# RVP_OVP_LC.net
KiCad netlist of a schematic drawn in Altium Designer
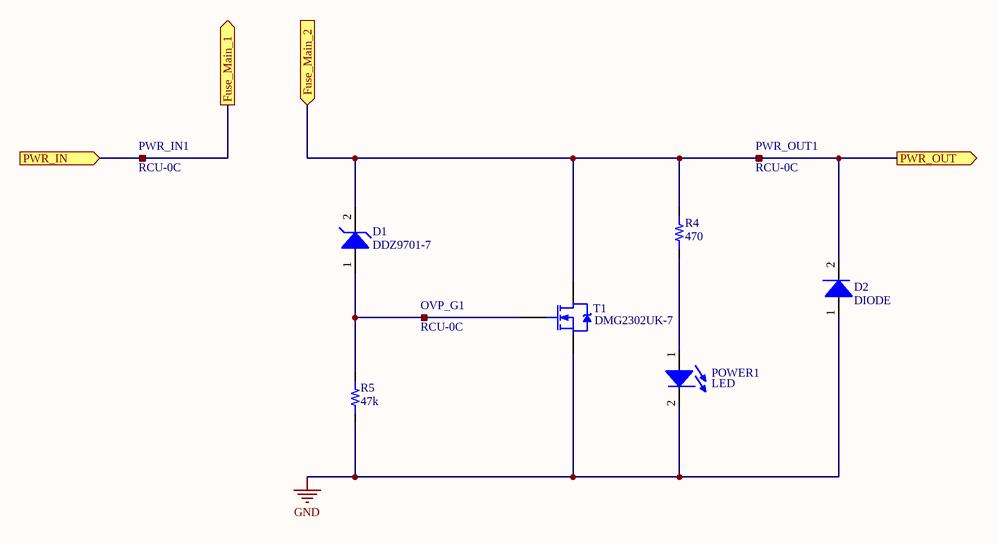
[diagram p0: RVP_OVP_LC.SchDoc]

(export (version "E")
  (design (tool "Eeschema 10.0.6"))
  (components
    (comp (ref "D1")
      (value "DDZ9701-7")
      (footprint "SOD123F")
      (description "Zener Diode 14V 500mW ±5% Surface Mount SOD-123")
      (fields (field (name "POWER") "500mW"))
      (libsource (lib "Altium-Lib") (part "Zener"))
    )
    (comp (ref "D2")
      (value "DIODE")
      (footprint "SOD-128")
      (description "DIODE SCHOTTKY 30V 5A TMINIP2")
      (fields (field (name "POWER") "30V") (field (name "MFRPARTNO") "DB2431200L"))
      (libsource (lib "Altium-Lib") (part "DIODE"))
    )
    (comp (ref "OVP_G1") (value "RCU-0C") (footprint "RCU-0C") (libsource (lib "Altium-Lib") (part "RCU-0C")))
    (comp (ref "POWER1") (value "LED") (footprint "0805_LED") (libsource (lib "Altium-Lib") (part "LED")))
    (comp (ref "PWR_IN1")
      (value "RCU-0C")
      (footprint "RCU-0C")
      (libsource (lib "Altium-Lib") (part "RCU-0C"))
    )
    (comp (ref "PWR_OUT1")
      (value "RCU-0C")
      (footprint "RCU-0C")
      (libsource (lib "Altium-Lib") (part "RCU-0C"))
    )
    (comp (ref "R4")
      (value "470")
      (footprint "RES 0805/2012")
      (fields
        (field (name "TOLERANCE") "1%")
        (field (name "POWER") "1/10W")
        (field (name "Comment") "Resistor 470 0805 1/10W 1%")
        (field (name "CREATED_BY") "Nick Mah")
      )
      (libsource (lib "Altium-Lib") (part "Resistor"))
    )
    (comp (ref "R5")
      (value "47k")
      (footprint "RES 0805/2012")
      (fields
        (field (name "TOLERANCE") "1%")
        (field (name "POWER") "1/10W")
        (field (name "Comment") "Resistor 47k 0805 1/10W 1%")
        (field (name "CREATED_BY") "Nick Mah")
      )
      (libsource (lib "Altium-Lib") (part "Resistor"))
    )
    (comp (ref "T1")
      (value "DMG2302UK-7")
      (footprint "SOT23-3")
      (description "MOSFET N-CHANNEL 30V 5A SOT23")
      (fields (field (name "CREATED_BY") "Angel"))
      (libsource (lib "Altium-Lib") (part "DMG2302UK-7"))
    )
  )
  (nets
    (net (code "1") (name "/Fuse_Main_1") (class "Default")
      (node (ref "PWR_IN1") (pin "1") (pintype "passive"))
    )
    (net (code "2") (name "/Fuse_Main_2") (class "Default")
      (node (ref "D1") (pin "2") (pinfunction "K_2") (pintype "passive"))
      (node (ref "D2") (pin "2") (pinfunction "K_2") (pintype "passive"))
      (node (ref "PWR_OUT1") (pin "1") (pintype "passive"))
      (node (ref "R4") (pin "2") (pinfunction "2_2") (pintype "passive"))
      (node (ref "T1") (pin "3") (pinfunction "D_3") (pintype "passive"))
    )
    (net (code "3") (name "GND") (class "Default")
      (node (ref "D2") (pin "1") (pinfunction "A_1") (pintype "passive"))
      (node (ref "POWER1") (pin "2") (pinfunction "K_2") (pintype "passive"))
      (node (ref "R5") (pin "1") (pinfunction "1_1") (pintype "passive"))
      (node (ref "T1") (pin "2") (pinfunction "S_2") (pintype "passive"))
    )
    (net (code "4") (name "Net-(D1-A)") (class "Default")
      (node (ref "D1") (pin "1") (pinfunction "A_1") (pintype "passive"))
      (node (ref "OVP_G1") (pin "1") (pintype "passive"))
      (node (ref "R5") (pin "2") (pinfunction "2_2") (pintype "passive"))
      (node (ref "T1") (pin "1") (pinfunction "G_1") (pintype "passive"))
    )
    (net (code "5") (name "Net-(POWER1-A)") (class "Default")
      (node (ref "POWER1") (pin "1") (pinfunction "A_1") (pintype "passive"))
      (node (ref "R4") (pin "1") (pinfunction "1_1") (pintype "passive"))
    )
  )
)
